# Sheet1.net
KiCad netlist of a schematic drawn in Altium Designer
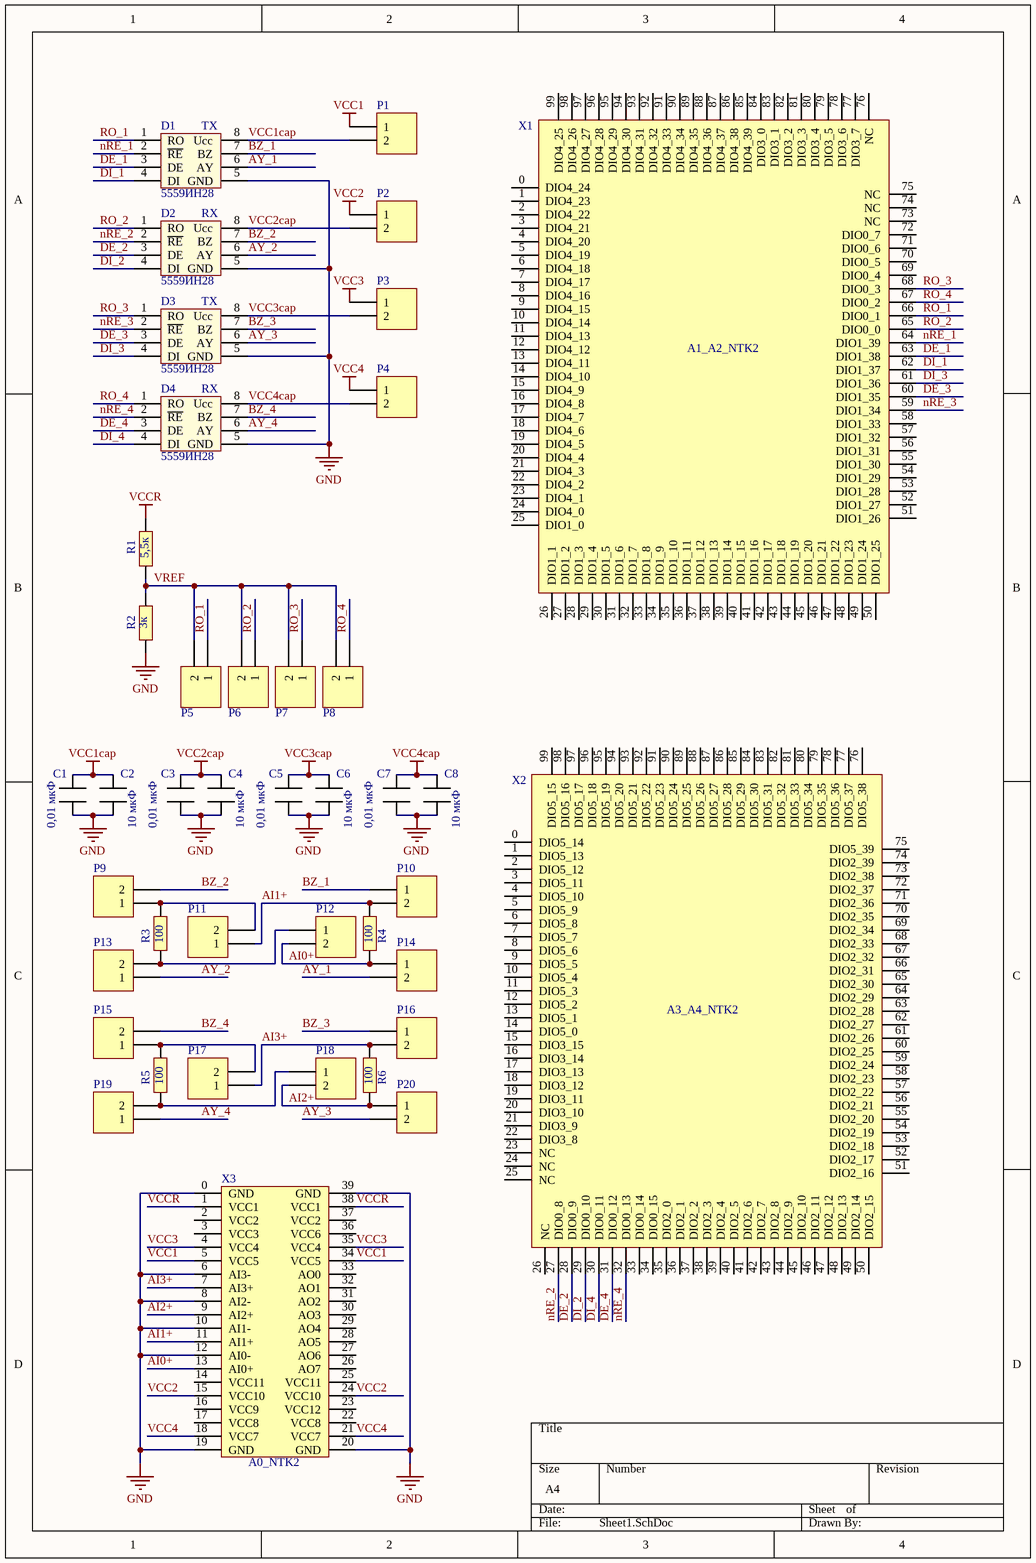
[diagram p0: Sheet1.SchDoc]

(export (version "E")
  (design (tool "Eeschema 10.0.6"))
  (components
    (comp (ref "C1") (value "0,01 мкФ") (footprint "CAP_SMALL") (libsource (lib "Schlib") (part "CAP_SMALL")))
    (comp (ref "C2") (value "10 мкФ") (footprint "Cap_BIG") (libsource (lib "Schlib") (part "CAP_BIG")))
    (comp (ref "C3") (value "0,01 мкФ") (footprint "CAP_SMALL") (libsource (lib "Schlib") (part "CAP_SMALL")))
    (comp (ref "C4") (value "10 мкФ") (footprint "Cap_BIG") (libsource (lib "Schlib") (part "CAP_BIG")))
    (comp (ref "C5") (value "0,01 мкФ") (footprint "CAP_SMALL") (libsource (lib "Schlib") (part "CAP_SMALL")))
    (comp (ref "C6") (value "10 мкФ") (footprint "Cap_BIG") (libsource (lib "Schlib") (part "CAP_BIG")))
    (comp (ref "C7") (value "0,01 мкФ") (footprint "CAP_SMALL") (libsource (lib "Schlib") (part "CAP_SMALL")))
    (comp (ref "C8") (value "10 мкФ") (footprint "Cap_BIG") (libsource (lib "Schlib") (part "CAP_BIG")))
    (comp (ref "D1") (value "5559ИН28") (footprint "5559IN28") (libsource (lib "VPL") (part "5559ИН28")))
    (comp (ref "D2") (value "5559ИН28") (footprint "5559IN28") (libsource (lib "VPL") (part "5559ИН28")))
    (comp (ref "D3") (value "5559ИН28") (footprint "5559IN28") (libsource (lib "VPL") (part "5559ИН28")))
    (comp (ref "D4") (value "5559ИН28") (footprint "5559IN28") (libsource (lib "VPL") (part "5559ИН28")))
    (comp (ref "P1")
      (value "Header 2")
      (footprint "HDR1X2")
      (description "Header, 2-Pin")
      (fields (field (name "PUBLISHER") "Altium Limited"))
      (libsource (lib "Miscellaneous Connectors") (part "Header 2"))
    )
    (comp (ref "P2")
      (value "Header 2")
      (footprint "HDR1X2")
      (description "Header, 2-Pin")
      (fields (field (name "PUBLISHER") "Altium Limited"))
      (libsource (lib "Miscellaneous Connectors") (part "Header 2"))
    )
    (comp (ref "P3")
      (value "Header 2")
      (footprint "HDR1X2")
      (description "Header, 2-Pin")
      (fields (field (name "PUBLISHER") "Altium Limited"))
      (libsource (lib "Miscellaneous Connectors") (part "Header 2"))
    )
    (comp (ref "P4")
      (value "Header 2")
      (footprint "HDR1X2")
      (description "Header, 2-Pin")
      (fields (field (name "PUBLISHER") "Altium Limited"))
      (libsource (lib "Miscellaneous Connectors") (part "Header 2"))
    )
    (comp (ref "P5")
      (value "Header 2")
      (footprint "HDR1X2")
      (description "Header, 2-Pin")
      (fields (field (name "PUBLISHER") "Altium Limited"))
      (libsource (lib "") (part "Header 2_2"))
    )
    (comp (ref "P6")
      (value "Header 2")
      (footprint "HDR1X2")
      (description "Header, 2-Pin")
      (fields (field (name "PUBLISHER") "Altium Limited"))
      (libsource (lib "") (part "Header 2_2"))
    )
    (comp (ref "P7")
      (value "Header 2")
      (footprint "HDR1X2")
      (description "Header, 2-Pin")
      (fields (field (name "PUBLISHER") "Altium Limited"))
      (libsource (lib "") (part "Header 2_2"))
    )
    (comp (ref "P8")
      (value "Header 2")
      (footprint "HDR1X2")
      (description "Header, 2-Pin")
      (fields (field (name "PUBLISHER") "Altium Limited"))
      (libsource (lib "") (part "Header 2_2"))
    )
    (comp (ref "P9")
      (value "Header 2")
      (footprint "HDR1X2")
      (description "Header, 2-Pin")
      (fields (field (name "PUBLISHER") "Altium Limited"))
      (libsource (lib "") (part "Header 2_1"))
    )
    (comp (ref "P10")
      (value "Header 2")
      (footprint "HDR1X2")
      (description "Header, 2-Pin")
      (fields (field (name "PUBLISHER") "Altium Limited"))
      (libsource (lib "Miscellaneous Connectors") (part "Header 2"))
    )
    (comp (ref "P11")
      (value "Header 2")
      (footprint "HDR1X2")
      (description "Header, 2-Pin")
      (fields (field (name "PUBLISHER") "Altium Limited"))
      (libsource (lib "") (part "Header 2_1"))
    )
    (comp (ref "P12")
      (value "Header 2")
      (footprint "HDR1X2")
      (description "Header, 2-Pin")
      (fields (field (name "PUBLISHER") "Altium Limited"))
      (libsource (lib "Miscellaneous Connectors") (part "Header 2"))
    )
    (comp (ref "P13")
      (value "Header 2")
      (footprint "HDR1X2")
      (description "Header, 2-Pin")
      (fields (field (name "PUBLISHER") "Altium Limited"))
      (libsource (lib "") (part "Header 2_1"))
    )
    (comp (ref "P14")
      (value "Header 2")
      (footprint "HDR1X2")
      (description "Header, 2-Pin")
      (fields (field (name "PUBLISHER") "Altium Limited"))
      (libsource (lib "Miscellaneous Connectors") (part "Header 2"))
    )
    (comp (ref "P15")
      (value "Header 2")
      (footprint "HDR1X2")
      (description "Header, 2-Pin")
      (fields (field (name "PUBLISHER") "Altium Limited"))
      (libsource (lib "") (part "Header 2_1"))
    )
    (comp (ref "P16")
      (value "Header 2")
      (footprint "HDR1X2")
      (description "Header, 2-Pin")
      (fields (field (name "PUBLISHER") "Altium Limited"))
      (libsource (lib "Miscellaneous Connectors") (part "Header 2"))
    )
    (comp (ref "P17")
      (value "Header 2")
      (footprint "HDR1X2")
      (description "Header, 2-Pin")
      (fields (field (name "PUBLISHER") "Altium Limited"))
      (libsource (lib "") (part "Header 2_1"))
    )
    (comp (ref "P18")
      (value "Header 2")
      (footprint "HDR1X2")
      (description "Header, 2-Pin")
      (fields (field (name "PUBLISHER") "Altium Limited"))
      (libsource (lib "Miscellaneous Connectors") (part "Header 2"))
    )
    (comp (ref "P19")
      (value "Header 2")
      (footprint "HDR1X2")
      (description "Header, 2-Pin")
      (fields (field (name "PUBLISHER") "Altium Limited"))
      (libsource (lib "") (part "Header 2_1"))
    )
    (comp (ref "P20")
      (value "Header 2")
      (footprint "HDR1X2")
      (description "Header, 2-Pin")
      (fields (field (name "PUBLISHER") "Altium Limited"))
      (libsource (lib "Miscellaneous Connectors") (part "Header 2"))
    )
    (comp (ref "R1") (value "5,5к") (footprint "RES") (libsource (lib "Schlib") (part "RES")))
    (comp (ref "R2") (value "3к") (footprint "RES") (libsource (lib "Schlib") (part "RES")))
    (comp (ref "R3") (value "100") (footprint "RES") (libsource (lib "") (part "RES_1")))
    (comp (ref "R4") (value "100") (footprint "RES") (libsource (lib "Schlib") (part "RES")))
    (comp (ref "R5") (value "100") (footprint "RES") (libsource (lib "") (part "RES_1")))
    (comp (ref "R6") (value "100") (footprint "RES") (libsource (lib "Schlib") (part "RES")))
    (comp (ref "X1")
      (value "A1_A2_NTK2")
      (footprint "A1_A2_NTK2")
      (libsource (lib "VPL") (part "A1_A2_NTK2"))
    )
    (comp (ref "X2")
      (value "A3_A4_NTK2")
      (footprint "A3_A4_NTK2")
      (libsource (lib "VPL") (part "A3_A4_NTK2"))
    )
    (comp (ref "X3") (value "A0_NTK2") (footprint "A0_NTK2") (libsource (lib "VPL") (part "A0_NTK2")))
  )
  (nets
    (net (code "1") (name "/AI0+") (class "Default")
      (node (ref "P12") (pin "2") (pinfunction "2_2") (pintype "passive"))
      (node (ref "P14") (pin "1") (pinfunction "1_1") (pintype "passive"))
      (node (ref "R4") (pin "2") (pinfunction "2_2") (pintype "passive"))
      (node (ref "X3") (pin "13") (pinfunction "AI0+_13") (pintype "power_in"))
    )
    (net (code "2") (name "/AI1+") (class "Default")
      (node (ref "P10") (pin "2") (pinfunction "2_2") (pintype "passive"))
      (node (ref "P11") (pin "1") (pinfunction "1_1") (pintype "passive"))
      (node (ref "R4") (pin "1") (pinfunction "1_1") (pintype "passive"))
      (node (ref "X3") (pin "11") (pinfunction "AI1+_11") (pintype "power_in"))
    )
    (net (code "3") (name "/AI2+") (class "Default")
      (node (ref "P18") (pin "2") (pinfunction "2_2") (pintype "passive"))
      (node (ref "P20") (pin "1") (pinfunction "1_1") (pintype "passive"))
      (node (ref "R6") (pin "2") (pinfunction "2_2") (pintype "passive"))
      (node (ref "X3") (pin "9") (pinfunction "AI2+_9") (pintype "power_in"))
    )
    (net (code "4") (name "/AI3+") (class "Default")
      (node (ref "P16") (pin "2") (pinfunction "2_2") (pintype "passive"))
      (node (ref "P17") (pin "1") (pinfunction "1_1") (pintype "passive"))
      (node (ref "R6") (pin "1") (pinfunction "1_1") (pintype "passive"))
      (node (ref "X3") (pin "7") (pinfunction "AI3+_7") (pintype "power_in"))
    )
    (net (code "5") (name "/AY_1") (class "Default")
      (node (ref "D1") (pin "6") (pinfunction "AY_6") (pintype "passive"))
      (node (ref "P14") (pin "2") (pinfunction "2_2") (pintype "passive"))
    )
    (net (code "6") (name "/AY_2") (class "Default")
      (node (ref "D2") (pin "6") (pinfunction "AY_6") (pintype "passive"))
      (node (ref "P13") (pin "1") (pinfunction "1_1") (pintype "passive"))
    )
    (net (code "7") (name "/AY_3") (class "Default")
      (node (ref "D3") (pin "6") (pinfunction "AY_6") (pintype "passive"))
      (node (ref "P20") (pin "2") (pinfunction "2_2") (pintype "passive"))
    )
    (net (code "8") (name "/AY_4") (class "Default")
      (node (ref "D4") (pin "6") (pinfunction "AY_6") (pintype "passive"))
      (node (ref "P19") (pin "1") (pinfunction "1_1") (pintype "passive"))
    )
    (net (code "9") (name "/BZ_1") (class "Default")
      (node (ref "D1") (pin "7") (pinfunction "BZ_7") (pintype "passive"))
      (node (ref "P10") (pin "1") (pinfunction "1_1") (pintype "passive"))
    )
    (net (code "10") (name "/BZ_2") (class "Default")
      (node (ref "D2") (pin "7") (pinfunction "BZ_7") (pintype "passive"))
      (node (ref "P9") (pin "2") (pinfunction "2_2") (pintype "passive"))
    )
    (net (code "11") (name "/BZ_3") (class "Default")
      (node (ref "D3") (pin "7") (pinfunction "BZ_7") (pintype "passive"))
      (node (ref "P16") (pin "1") (pinfunction "1_1") (pintype "passive"))
    )
    (net (code "12") (name "/BZ_4") (class "Default")
      (node (ref "D4") (pin "7") (pinfunction "BZ_7") (pintype "passive"))
      (node (ref "P15") (pin "2") (pinfunction "2_2") (pintype "passive"))
    )
    (net (code "13") (name "/DE_1") (class "Default")
      (node (ref "D1") (pin "3") (pinfunction "DE_3") (pintype "passive"))
      (node (ref "X1") (pin "63") (pinfunction "DIO1_38_63") (pintype "power_in"))
    )
    (net (code "14") (name "/DE_2") (class "Default")
      (node (ref "D2") (pin "3") (pinfunction "DE_3") (pintype "passive"))
      (node (ref "X2") (pin "28") (pinfunction "DIO0_9_28") (pintype "power_in"))
    )
    (net (code "15") (name "/DE_3") (class "Default")
      (node (ref "D3") (pin "3") (pinfunction "DE_3") (pintype "passive"))
      (node (ref "X1") (pin "60") (pinfunction "DIO1_35_60") (pintype "power_in"))
    )
    (net (code "16") (name "/DE_4") (class "Default")
      (node (ref "D4") (pin "3") (pinfunction "DE_3") (pintype "passive"))
      (node (ref "X2") (pin "31") (pinfunction "DIO0_12_31") (pintype "power_in"))
    )
    (net (code "17") (name "/DI_1") (class "Default")
      (node (ref "D1") (pin "4") (pinfunction "DI_4") (pintype "passive"))
      (node (ref "X1") (pin "62") (pinfunction "DIO1_37_62") (pintype "power_in"))
    )
    (net (code "18") (name "/DI_2") (class "Default")
      (node (ref "D2") (pin "4") (pinfunction "DI_4") (pintype "passive"))
      (node (ref "X2") (pin "29") (pinfunction "DIO0_10_29") (pintype "power_in"))
    )
    (net (code "19") (name "/DI_3") (class "Default")
      (node (ref "D3") (pin "4") (pinfunction "DI_4") (pintype "passive"))
      (node (ref "X1") (pin "61") (pinfunction "DIO1_36_61") (pintype "power_in"))
    )
    (net (code "20") (name "/DI_4") (class "Default")
      (node (ref "D4") (pin "4") (pinfunction "DI_4") (pintype "passive"))
      (node (ref "X2") (pin "30") (pinfunction "DIO0_11_30") (pintype "power_in"))
    )
    (net (code "21") (name "/RO_1") (class "Default")
      (node (ref "D1") (pin "1") (pinfunction "RO_1") (pintype "passive"))
      (node (ref "P5") (pin "1") (pinfunction "1_1") (pintype "passive"))
      (node (ref "X1") (pin "66") (pinfunction "DIO0_1_66") (pintype "power_in"))
    )
    (net (code "22") (name "/RO_2") (class "Default")
      (node (ref "D2") (pin "1") (pinfunction "RO_1") (pintype "passive"))
      (node (ref "P6") (pin "1") (pinfunction "1_1") (pintype "passive"))
      (node (ref "X1") (pin "65") (pinfunction "DIO0_0_65") (pintype "power_in"))
    )
    (net (code "23") (name "/RO_3") (class "Default")
      (node (ref "D3") (pin "1") (pinfunction "RO_1") (pintype "passive"))
      (node (ref "P7") (pin "1") (pinfunction "1_1") (pintype "passive"))
      (node (ref "X1") (pin "68") (pinfunction "DIO0_3_68") (pintype "power_in"))
    )
    (net (code "24") (name "/RO_4") (class "Default")
      (node (ref "D4") (pin "1") (pinfunction "RO_1") (pintype "passive"))
      (node (ref "P8") (pin "1") (pinfunction "1_1") (pintype "passive"))
      (node (ref "X1") (pin "67") (pinfunction "DIO0_2_67") (pintype "power_in"))
    )
    (net (code "25") (name "/VREF") (class "Default")
      (node (ref "P5") (pin "2") (pinfunction "2_2") (pintype "passive"))
      (node (ref "P6") (pin "2") (pinfunction "2_2") (pintype "passive"))
      (node (ref "P7") (pin "2") (pinfunction "2_2") (pintype "passive"))
      (node (ref "P8") (pin "2") (pinfunction "2_2") (pintype "passive"))
      (node (ref "R1") (pin "2") (pinfunction "2_2") (pintype "passive"))
      (node (ref "R2") (pin "1") (pinfunction "1_1") (pintype "passive"))
    )
    (net (code "26") (name "/nRE_1") (class "Default")
      (node (ref "D1") (pin "2") (pinfunction "~{RE}_2") (pintype "passive"))
      (node (ref "X1") (pin "64") (pinfunction "DIO1_39_64") (pintype "power_in"))
    )
    (net (code "27") (name "/nRE_2") (class "Default")
      (node (ref "D2") (pin "2") (pinfunction "~{RE}_2") (pintype "passive"))
      (node (ref "X2") (pin "27") (pinfunction "DIO0_8_27") (pintype "power_in"))
    )
    (net (code "28") (name "/nRE_3") (class "Default")
      (node (ref "D3") (pin "2") (pinfunction "~{RE}_2") (pintype "passive"))
      (node (ref "X1") (pin "59") (pinfunction "DIO1_34_59") (pintype "power_in"))
    )
    (net (code "29") (name "/nRE_4") (class "Default")
      (node (ref "D4") (pin "2") (pinfunction "~{RE}_2") (pintype "passive"))
      (node (ref "X2") (pin "32") (pinfunction "DIO0_13_32") (pintype "power_in"))
    )
    (net (code "30") (name "GND") (class "Default")
      (node (ref "C1") (pin "1") (pinfunction "1_1") (pintype "passive"))
      (node (ref "C2") (pin "1") (pinfunction "1_1") (pintype "passive"))
      (node (ref "C3") (pin "1") (pinfunction "1_1") (pintype "passive"))
      (node (ref "C4") (pin "1") (pinfunction "1_1") (pintype "passive"))
      (node (ref "C5") (pin "1") (pinfunction "1_1") (pintype "passive"))
      (node (ref "C6") (pin "1") (pinfunction "1_1") (pintype "passive"))
      (node (ref "C7") (pin "1") (pinfunction "1_1") (pintype "passive"))
      (node (ref "C8") (pin "1") (pinfunction "1_1") (pintype "passive"))
      (node (ref "D1") (pin "5") (pinfunction "GND_5") (pintype "passive"))
      (node (ref "D2") (pin "5") (pinfunction "GND_5") (pintype "passive"))
      (node (ref "D3") (pin "5") (pinfunction "GND_5") (pintype "passive"))
      (node (ref "D4") (pin "5") (pinfunction "GND_5") (pintype "passive"))
      (node (ref "R2") (pin "2") (pinfunction "2_2") (pintype "passive"))
      (node (ref "X3") (pin "0") (pinfunction "GND_0") (pintype "power_in"))
      (node (ref "X3") (pin "10") (pinfunction "AI1-_10") (pintype "power_in"))
      (node (ref "X3") (pin "12") (pinfunction "AI0-_12") (pintype "power_in"))
      (node (ref "X3") (pin "19") (pinfunction "GND_19") (pintype "power_in"))
      (node (ref "X3") (pin "20") (pinfunction "GND_20") (pintype "power_in"))
      (node (ref "X3") (pin "39") (pinfunction "GND_39") (pintype "power_in"))
      (node (ref "X3") (pin "6") (pinfunction "AI3-_6") (pintype "power_in"))
      (node (ref "X3") (pin "8") (pinfunction "AI2-_8") (pintype "power_in"))
    )
    (net (code "31") (name "Net-(P11-Pad2)") (class "Default")
      (node (ref "P11") (pin "2") (pinfunction "2_2") (pintype "passive"))
      (node (ref "P9") (pin "1") (pinfunction "1_1") (pintype "passive"))
      (node (ref "R3") (pin "2") (pinfunction "2_2") (pintype "passive"))
    )
    (net (code "32") (name "Net-(P12-Pad1)") (class "Default")
      (node (ref "P12") (pin "1") (pinfunction "1_1") (pintype "passive"))
      (node (ref "P13") (pin "2") (pinfunction "2_2") (pintype "passive"))
      (node (ref "R3") (pin "1") (pinfunction "1_1") (pintype "passive"))
    )
    (net (code "33") (name "Net-(P15-Pad1)") (class "Default")
      (node (ref "P15") (pin "1") (pinfunction "1_1") (pintype "passive"))
      (node (ref "P17") (pin "2") (pinfunction "2_2") (pintype "passive"))
      (node (ref "R5") (pin "2") (pinfunction "2_2") (pintype "passive"))
    )
    (net (code "34") (name "Net-(P18-Pad1)") (class "Default")
      (node (ref "P18") (pin "1") (pinfunction "1_1") (pintype "passive"))
      (node (ref "P19") (pin "2") (pinfunction "2_2") (pintype "passive"))
      (node (ref "R5") (pin "1") (pinfunction "1_1") (pintype "passive"))
    )
    (net (code "35") (name "VCC1") (class "Default")
      (node (ref "P1") (pin "1") (pinfunction "1_1") (pintype "passive"))
      (node (ref "X3") (pin "34") (pinfunction "VCC5_34") (pintype "power_in"))
      (node (ref "X3") (pin "5") (pinfunction "VCC5_5") (pintype "power_in"))
    )
    (net (code "36") (name "VCC1cap") (class "Default")
      (node (ref "C1") (pin "2") (pinfunction "2_2") (pintype "passive"))
      (node (ref "C2") (pin "2") (pinfunction "2_2") (pintype "passive"))
      (node (ref "D1") (pin "8") (pinfunction "Ucc_8") (pintype "passive"))
      (node (ref "P1") (pin "2") (pinfunction "2_2") (pintype "passive"))
    )
    (net (code "37") (name "VCC2") (class "Default")
      (node (ref "P2") (pin "1") (pinfunction "1_1") (pintype "passive"))
      (node (ref "X3") (pin "15") (pinfunction "VCC10_15") (pintype "power_in"))
      (node (ref "X3") (pin "24") (pinfunction "VCC10_24") (pintype "power_in"))
    )
    (net (code "38") (name "VCC2cap") (class "Default")
      (node (ref "C3") (pin "2") (pinfunction "2_2") (pintype "passive"))
      (node (ref "C4") (pin "2") (pinfunction "2_2") (pintype "passive"))
      (node (ref "D2") (pin "8") (pinfunction "Ucc_8") (pintype "passive"))
      (node (ref "P2") (pin "2") (pinfunction "2_2") (pintype "passive"))
    )
    (net (code "39") (name "VCC3") (class "Default")
      (node (ref "P3") (pin "1") (pinfunction "1_1") (pintype "passive"))
      (node (ref "X3") (pin "35") (pinfunction "VCC4_35") (pintype "power_in"))
      (node (ref "X3") (pin "4") (pinfunction "VCC4_4") (pintype "power_in"))
    )
    (net (code "40") (name "VCC3cap") (class "Default")
      (node (ref "C5") (pin "2") (pinfunction "2_2") (pintype "passive"))
      (node (ref "C6") (pin "2") (pinfunction "2_2") (pintype "passive"))
      (node (ref "D3") (pin "8") (pinfunction "Ucc_8") (pintype "passive"))
      (node (ref "P3") (pin "2") (pinfunction "2_2") (pintype "passive"))
    )
    (net (code "41") (name "VCC4") (class "Default")
      (node (ref "P4") (pin "1") (pinfunction "1_1") (pintype "passive"))
      (node (ref "X3") (pin "18") (pinfunction "VCC7_18") (pintype "power_in"))
      (node (ref "X3") (pin "21") (pinfunction "VCC7_21") (pintype "power_in"))
    )
    (net (code "42") (name "VCC4cap") (class "Default")
      (node (ref "C7") (pin "2") (pinfunction "2_2") (pintype "passive"))
      (node (ref "C8") (pin "2") (pinfunction "2_2") (pintype "passive"))
      (node (ref "D4") (pin "8") (pinfunction "Ucc_8") (pintype "passive"))
      (node (ref "P4") (pin "2") (pinfunction "2_2") (pintype "passive"))
    )
    (net (code "43") (name "VCCR") (class "Default")
      (node (ref "R1") (pin "1") (pinfunction "1_1") (pintype "passive"))
      (node (ref "X3") (pin "1") (pinfunction "VCC1_1") (pintype "power_in"))
      (node (ref "X3") (pin "38") (pinfunction "VCC1_38") (pintype "power_in"))
    )
    (net (code "44") (name "unconnected-(X1-DIO0_4-Pad69)") (class "Default")
      (node (ref "X1") (pin "69") (pinfunction "DIO0_4_69") (pintype "power_in"))
    )
    (net (code "45") (name "unconnected-(X1-DIO0_5-Pad70)") (class "Default")
      (node (ref "X1") (pin "70") (pinfunction "DIO0_5_70") (pintype "power_in"))
    )
    (net (code "46") (name "unconnected-(X1-DIO0_6-Pad71)") (class "Default")
      (node (ref "X1") (pin "71") (pinfunction "DIO0_6_71") (pintype "power_in"))
    )
    (net (code "47") (name "unconnected-(X1-DIO0_7-Pad72)") (class "Default")
      (node (ref "X1") (pin "72") (pinfunction "DIO0_7_72") (pintype "power_in"))
    )
    (net (code "48") (name "unconnected-(X1-DIO1_0-Pad25)") (class "Default")
      (node (ref "X1") (pin "25") (pinfunction "DIO1_0_25") (pintype "power_in"))
    )
    (net (code "49") (name "unconnected-(X1-DIO1_1-Pad26)") (class "Default")
      (node (ref "X1") (pin "26") (pinfunction "DIO1_1_26") (pintype "power_in"))
    )
    (net (code "50") (name "unconnected-(X1-DIO1_2-Pad27)") (class "Default")
      (node (ref "X1") (pin "27") (pinfunction "DIO1_2_27") (pintype "power_in"))
    )
    (net (code "51") (name "unconnected-(X1-DIO1_3-Pad28)") (class "Default")
      (node (ref "X1") (pin "28") (pinfunction "DIO1_3_28") (pintype "power_in"))
    )
    (net (code "52") (name "unconnected-(X1-DIO1_4-Pad29)") (class "Default")
      (node (ref "X1") (pin "29") (pinfunction "DIO1_4_29") (pintype "power_in"))
    )
    (net (code "53") (name "unconnected-(X1-DIO1_5-Pad30)") (class "Default")
      (node (ref "X1") (pin "30") (pinfunction "DIO1_5_30") (pintype "power_in"))
    )
    (net (code "54") (name "unconnected-(X1-DIO1_6-Pad31)") (class "Default")
      (node (ref "X1") (pin "31") (pinfunction "DIO1_6_31") (pintype "power_in"))
    )
    (net (code "55") (name "unconnected-(X1-DIO1_7-Pad32)") (class "Default")
      (node (ref "X1") (pin "32") (pinfunction "DIO1_7_32") (pintype "power_in"))
    )
    (net (code "56") (name "unconnected-(X1-DIO1_8-Pad33)") (class "Default")
      (node (ref "X1") (pin "33") (pinfunction "DIO1_8_33") (pintype "power_in"))
    )
    (net (code "57") (name "unconnected-(X1-DIO1_9-Pad34)") (class "Default")
      (node (ref "X1") (pin "34") (pinfunction "DIO1_9_34") (pintype "power_in"))
    )
    (net (code "58") (name "unconnected-(X1-DIO1_10-Pad35)") (class "Default")
      (node (ref "X1") (pin "35") (pinfunction "DIO1_10_35") (pintype "power_in"))
    )
    (net (code "59") (name "unconnected-(X1-DIO1_11-Pad36)") (class "Default")
      (node (ref "X1") (pin "36") (pinfunction "DIO1_11_36") (pintype "power_in"))
    )
    (net (code "60") (name "unconnected-(X1-DIO1_12-Pad37)") (class "Default")
      (node (ref "X1") (pin "37") (pinfunction "DIO1_12_37") (pintype "power_in"))
    )
    (net (code "61") (name "unconnected-(X1-DIO1_13-Pad38)") (class "Default")
      (node (ref "X1") (pin "38") (pinfunction "DIO1_13_38") (pintype "power_in"))
    )
    (net (code "62") (name "unconnected-(X1-DIO1_14-Pad39)") (class "Default")
      (node (ref "X1") (pin "39") (pinfunction "DIO1_14_39") (pintype "power_in"))
    )
    (net (code "63") (name "unconnected-(X1-DIO1_15-Pad40)") (class "Default")
      (node (ref "X1") (pin "40") (pinfunction "DIO1_15_40") (pintype "power_in"))
    )
    (net (code "64") (name "unconnected-(X1-DIO1_16-Pad41)") (class "Default")
      (node (ref "X1") (pin "41") (pinfunction "DIO1_16_41") (pintype "power_in"))
    )
    (net (code "65") (name "unconnected-(X1-DIO1_17-Pad42)") (class "Default")
      (node (ref "X1") (pin "42") (pinfunction "DIO1_17_42") (pintype "power_in"))
    )
    (net (code "66") (name "unconnected-(X1-DIO1_18-Pad43)") (class "Default")
      (node (ref "X1") (pin "43") (pinfunction "DIO1_18_43") (pintype "power_in"))
    )
    (net (code "67") (name "unconnected-(X1-DIO1_19-Pad44)") (class "Default")
      (node (ref "X1") (pin "44") (pinfunction "DIO1_19_44") (pintype "power_in"))
    )
    (net (code "68") (name "unconnected-(X1-DIO1_20-Pad45)") (class "Default")
      (node (ref "X1") (pin "45") (pinfunction "DIO1_20_45") (pintype "power_in"))
    )
    (net (code "69") (name "unconnected-(X1-DIO1_21-Pad46)") (class "Default")
      (node (ref "X1") (pin "46") (pinfunction "DIO1_21_46") (pintype "power_in"))
    )
    (net (code "70") (name "unconnected-(X1-DIO1_22-Pad47)") (class "Default")
      (node (ref "X1") (pin "47") (pinfunction "DIO1_22_47") (pintype "power_in"))
    )
    (net (code "71") (name "unconnected-(X1-DIO1_23-Pad48)") (class "Default")
      (node (ref "X1") (pin "48") (pinfunction "DIO1_23_48") (pintype "power_in"))
    )
    (net (code "72") (name "unconnected-(X1-DIO1_24-Pad49)") (class "Default")
      (node (ref "X1") (pin "49") (pinfunction "DIO1_24_49") (pintype "power_in"))
    )
    (net (code "73") (name "unconnected-(X1-DIO1_25-Pad50)") (class "Default")
      (node (ref "X1") (pin "50") (pinfunction "DIO1_25_50") (pintype "power_in"))
    )
    (net (code "74") (name "unconnected-(X1-DIO1_26-Pad51)") (class "Default")
      (node (ref "X1") (pin "51") (pinfunction "DIO1_26_51") (pintype "power_in"))
    )
    (net (code "75") (name "unconnected-(X1-DIO1_27-Pad52)") (class "Default")
      (node (ref "X1") (pin "52") (pinfunction "DIO1_27_52") (pintype "power_in"))
    )
    (net (code "76") (name "unconnected-(X1-DIO1_28-Pad53)") (class "Default")
      (node (ref "X1") (pin "53") (pinfunction "DIO1_28_53") (pintype "power_in"))
    )
    (net (code "77") (name "unconnected-(X1-DIO1_29-Pad54)") (class "Default")
      (node (ref "X1") (pin "54") (pinfunction "DIO1_29_54") (pintype "power_in"))
    )
    (net (code "78") (name "unconnected-(X1-DIO1_30-Pad55)") (class "Default")
      (node (ref "X1") (pin "55") (pinfunction "DIO1_30_55") (pintype "power_in"))
    )
    (net (code "79") (name "unconnected-(X1-DIO1_31-Pad56)") (class "Default")
      (node (ref "X1") (pin "56") (pinfunction "DIO1_31_56") (pintype "power_in"))
    )
    (net (code "80") (name "unconnected-(X1-DIO1_32-Pad57)") (class "Default")
      (node (ref "X1") (pin "57") (pinfunction "DIO1_32_57") (pintype "power_in"))
    )
    (net (code "81") (name "unconnected-(X1-DIO1_33-Pad58)") (class "Default")
      (node (ref "X1") (pin "58") (pinfunction "DIO1_33_58") (pintype "power_in"))
    )
    (net (code "82") (name "unconnected-(X1-DIO3_0-Pad84)") (class "Default")
      (node (ref "X1") (pin "84") (pinfunction "DIO3_0_84") (pintype "power_in"))
    )
    (net (code "83") (name "unconnected-(X1-DIO3_1-Pad83)") (class "Default")
      (node (ref "X1") (pin "83") (pinfunction "DIO3_1_83") (pintype "power_in"))
    )
    (net (code "84") (name "unconnected-(X1-DIO3_2-Pad82)") (class "Default")
      (node (ref "X1") (pin "82") (pinfunction "DIO3_2_82") (pintype "power_in"))
    )
    (net (code "85") (name "unconnected-(X1-DIO3_3-Pad81)") (class "Default")
      (node (ref "X1") (pin "81") (pinfunction "DIO3_3_81") (pintype "power_in"))
    )
    (net (code "86") (name "unconnected-(X1-DIO3_4-Pad80)") (class "Default")
      (node (ref "X1") (pin "80") (pinfunction "DIO3_4_80") (pintype "power_in"))
    )
    (net (code "87") (name "unconnected-(X1-DIO3_5-Pad79)") (class "Default")
      (node (ref "X1") (pin "79") (pinfunction "DIO3_5_79") (pintype "power_in"))
    )
    (net (code "88") (name "unconnected-(X1-DIO3_6-Pad78)") (class "Default")
      (node (ref "X1") (pin "78") (pinfunction "DIO3_6_78") (pintype "power_in"))
    )
    (net (code "89") (name "unconnected-(X1-DIO3_7-Pad77)") (class "Default")
      (node (ref "X1") (pin "77") (pinfunction "DIO3_7_77") (pintype "power_in"))
    )
    (net (code "90") (name "unconnected-(X1-DIO4_0-Pad24)") (class "Default")
      (node (ref "X1") (pin "24") (pinfunction "DIO4_0_24") (pintype "power_in"))
    )
    (net (code "91") (name "unconnected-(X1-DIO4_1-Pad23)") (class "Default")
      (node (ref "X1") (pin "23") (pinfunction "DIO4_1_23") (pintype "power_in"))
    )
    (net (code "92") (name "unconnected-(X1-DIO4_2-Pad22)") (class "Default")
      (node (ref "X1") (pin "22") (pinfunction "DIO4_2_22") (pintype "power_in"))
    )
    (net (code "93") (name "unconnected-(X1-DIO4_3-Pad21)") (class "Default")
      (node (ref "X1") (pin "21") (pinfunction "DIO4_3_21") (pintype "power_in"))
    )
    (net (code "94") (name "unconnected-(X1-DIO4_4-Pad20)") (class "Default")
      (node (ref "X1") (pin "20") (pinfunction "DIO4_4_20") (pintype "power_in"))
    )
    (net (code "95") (name "unconnected-(X1-DIO4_5-Pad19)") (class "Default")
      (node (ref "X1") (pin "19") (pinfunction "DIO4_5_19") (pintype "power_in"))
    )
    (net (code "96") (name "unconnected-(X1-DIO4_6-Pad18)") (class "Default")
      (node (ref "X1") (pin "18") (pinfunction "DIO4_6_18") (pintype "power_in"))
    )
    (net (code "97") (name "unconnected-(X1-DIO4_7-Pad17)") (class "Default")
      (node (ref "X1") (pin "17") (pinfunction "DIO4_7_17") (pintype "power_in"))
    )
    (net (code "98") (name "unconnected-(X1-DIO4_8-Pad16)") (class "Default")
      (node (ref "X1") (pin "16") (pinfunction "DIO4_8_16") (pintype "power_in"))
    )
    (net (code "99") (name "unconnected-(X1-DIO4_9-Pad15)") (class "Default")
      (node (ref "X1") (pin "15") (pinfunction "DIO4_9_15") (pintype "power_in"))
    )
    (net (code "100") (name "unconnected-(X1-DIO4_10-Pad14)") (class "Default")
      (node (ref "X1") (pin "14") (pinfunction "DIO4_10_14") (pintype "power_in"))
    )
    (net (code "101") (name "unconnected-(X1-DIO4_11-Pad13)") (class "Default")
      (node (ref "X1") (pin "13") (pinfunction "DIO4_11_13") (pintype "power_in"))
    )
    (net (code "102") (name "unconnected-(X1-DIO4_12-Pad12)") (class "Default")
      (node (ref "X1") (pin "12") (pinfunction "DIO4_12_12") (pintype "power_in"))
    )
    (net (code "103") (name "unconnected-(X1-DIO4_13-Pad11)") (class "Default")
      (node (ref "X1") (pin "11") (pinfunction "DIO4_13_11") (pintype "power_in"))
    )
    (net (code "104") (name "unconnected-(X1-DIO4_14-Pad10)") (class "Default")
      (node (ref "X1") (pin "10") (pinfunction "DIO4_14_10") (pintype "power_in"))
    )
    (net (code "105") (name "unconnected-(X1-DIO4_15-Pad9)") (class "Default")
      (node (ref "X1") (pin "9") (pinfunction "DIO4_15_9") (pintype "power_in"))
    )
    (net (code "106") (name "unconnected-(X1-DIO4_16-Pad8)") (class "Default")
      (node (ref "X1") (pin "8") (pinfunction "DIO4_16_8") (pintype "power_in"))
    )
    (net (code "107") (name "unconnected-(X1-DIO4_17-Pad7)") (class "Default")
      (node (ref "X1") (pin "7") (pinfunction "DIO4_17_7") (pintype "power_in"))
    )
    (net (code "108") (name "unconnected-(X1-DIO4_18-Pad6)") (class "Default")
      (node (ref "X1") (pin "6") (pinfunction "DIO4_18_6") (pintype "power_in"))
    )
    (net (code "109") (name "unconnected-(X1-DIO4_19-Pad5)") (class "Default")
      (node (ref "X1") (pin "5") (pinfunction "DIO4_19_5") (pintype "power_in"))
    )
    (net (code "110") (name "unconnected-(X1-DIO4_20-Pad4)") (class "Default")
      (node (ref "X1") (pin "4") (pinfunction "DIO4_20_4") (pintype "power_in"))
    )
    (net (code "111") (name "unconnected-(X1-DIO4_21-Pad3)") (class "Default")
      (node (ref "X1") (pin "3") (pinfunction "DIO4_21_3") (pintype "power_in"))
    )
    (net (code "112") (name "unconnected-(X1-DIO4_22-Pad2)") (class "Default")
      (node (ref "X1") (pin "2") (pinfunction "DIO4_22_2") (pintype "power_in"))
    )
    (net (code "113") (name "unconnected-(X1-DIO4_23-Pad1)") (class "Default")
      (node (ref "X1") (pin "1") (pinfunction "DIO4_23_1") (pintype "power_in"))
    )
    (net (code "114") (name "unconnected-(X1-DIO4_24-Pad0)") (class "Default")
      (node (ref "X1") (pin "0") (pinfunction "DIO4_24_0") (pintype "power_in"))
    )
    (net (code "115") (name "unconnected-(X1-DIO4_25-Pad99)") (class "Default")
      (node (ref "X1") (pin "99") (pinfunction "DIO4_25_99") (pintype "power_in"))
    )
    (net (code "116") (name "unconnected-(X1-DIO4_26-Pad98)") (class "Default")
      (node (ref "X1") (pin "98") (pinfunction "DIO4_26_98") (pintype "power_in"))
    )
    (net (code "117") (name "unconnected-(X1-DIO4_27-Pad97)") (class "Default")
      (node (ref "X1") (pin "97") (pinfunction "DIO4_27_97") (pintype "power_in"))
    )
    (net (code "118") (name "unconnected-(X1-DIO4_28-Pad96)") (class "Default")
      (node (ref "X1") (pin "96") (pinfunction "DIO4_28_96") (pintype "power_in"))
    )
    (net (code "119") (name "unconnected-(X1-DIO4_29-Pad95)") (class "Default")
      (node (ref "X1") (pin "95") (pinfunction "DIO4_29_95") (pintype "power_in"))
    )
    (net (code "120") (name "unconnected-(X1-DIO4_30-Pad94)") (class "Default")
      (node (ref "X1") (pin "94") (pinfunction "DIO4_30_94") (pintype "power_in"))
    )
    (net (code "121") (name "unconnected-(X1-DIO4_31-Pad93)") (class "Default")
      (node (ref "X1") (pin "93") (pinfunction "DIO4_31_93") (pintype "power_in"))
    )
    (net (code "122") (name "unconnected-(X1-DIO4_32-Pad92)") (class "Default")
      (node (ref "X1") (pin "92") (pinfunction "DIO4_32_92") (pintype "power_in"))
    )
    (net (code "123") (name "unconnected-(X1-DIO4_33-Pad91)") (class "Default")
      (node (ref "X1") (pin "91") (pinfunction "DIO4_33_91") (pintype "power_in"))
    )
    (net (code "124") (name "unconnected-(X1-DIO4_34-Pad90)") (class "Default")
      (node (ref "X1") (pin "90") (pinfunction "DIO4_34_90") (pintype "power_in"))
    )
    (net (code "125") (name "unconnected-(X1-DIO4_35-Pad89)") (class "Default")
      (node (ref "X1") (pin "89") (pinfunction "DIO4_35_89") (pintype "power_in"))
    )
    (net (code "126") (name "unconnected-(X1-DIO4_36-Pad88)") (class "Default")
      (node (ref "X1") (pin "88") (pinfunction "DIO4_36_88") (pintype "power_in"))
    )
    (net (code "127") (name "unconnected-(X1-DIO4_37-Pad87)") (class "Default")
      (node (ref "X1") (pin "87") (pinfunction "DIO4_37_87") (pintype "power_in"))
    )
    (net (code "128") (name "unconnected-(X1-DIO4_38-Pad86)") (class "Default")
      (node (ref "X1") (pin "86") (pinfunction "DIO4_38_86") (pintype "power_in"))
    )
    (net (code "129") (name "unconnected-(X1-DIO4_39-Pad85)") (class "Default")
      (node (ref "X1") (pin "85") (pinfunction "DIO4_39_85") (pintype "power_in"))
    )
    (net (code "130") (name "unconnected-(X1-NC-Pad73)") (class "Default")
      (node (ref "X1") (pin "73") (pinfunction "NC_73") (pintype "power_in"))
    )
    (net (code "131") (name "unconnected-(X1-NC-Pad74)") (class "Default")
      (node (ref "X1") (pin "74") (pinfunction "NC_74") (pintype "power_in"))
    )
    (net (code "132") (name "unconnected-(X1-NC-Pad75)") (class "Default")
      (node (ref "X1") (pin "75") (pinfunction "NC_75") (pintype "power_in"))
    )
    (net (code "133") (name "unconnected-(X1-NC-Pad76)") (class "Default")
      (node (ref "X1") (pin "76") (pinfunction "NC_76") (pintype "power_in"))
    )
    (net (code "134") (name "unconnected-(X2-DIO0_14-Pad33)") (class "Default")
      (node (ref "X2") (pin "33") (pinfunction "DIO0_14_33") (pintype "power_in"))
    )
    (net (code "135") (name "unconnected-(X2-DIO0_15-Pad34)") (class "Default")
      (node (ref "X2") (pin "34") (pinfunction "DIO0_15_34") (pintype "power_in"))
    )
    (net (code "136") (name "unconnected-(X2-DIO2_0-Pad35)") (class "Default")
      (node (ref "X2") (pin "35") (pinfunction "DIO2_0_35") (pintype "power_in"))
    )
    (net (code "137") (name "unconnected-(X2-DIO2_1-Pad36)") (class "Default")
      (node (ref "X2") (pin "36") (pinfunction "DIO2_1_36") (pintype "power_in"))
    )
    (net (code "138") (name "unconnected-(X2-DIO2_2-Pad37)") (class "Default")
      (node (ref "X2") (pin "37") (pinfunction "DIO2_2_37") (pintype "power_in"))
    )
    (net (code "139") (name "unconnected-(X2-DIO2_3-Pad38)") (class "Default")
      (node (ref "X2") (pin "38") (pinfunction "DIO2_3_38") (pintype "power_in"))
    )
    (net (code "140") (name "unconnected-(X2-DIO2_4-Pad39)") (class "Default")
      (node (ref "X2") (pin "39") (pinfunction "DIO2_4_39") (pintype "power_in"))
    )
    (net (code "141") (name "unconnected-(X2-DIO2_5-Pad40)") (class "Default")
      (node (ref "X2") (pin "40") (pinfunction "DIO2_5_40") (pintype "power_in"))
    )
    (net (code "142") (name "unconnected-(X2-DIO2_6-Pad41)") (class "Default")
      (node (ref "X2") (pin "41") (pinfunction "DIO2_6_41") (pintype "power_in"))
    )
    (net (code "143") (name "unconnected-(X2-DIO2_7-Pad42)") (class "Default")
      (node (ref "X2") (pin "42") (pinfunction "DIO2_7_42") (pintype "power_in"))
    )
    (net (code "144") (name "unconnected-(X2-DIO2_8-Pad43)") (class "Default")
      (node (ref "X2") (pin "43") (pinfunction "DIO2_8_43") (pintype "power_in"))
    )
    (net (code "145") (name "unconnected-(X2-DIO2_9-Pad44)") (class "Default")
      (node (ref "X2") (pin "44") (pinfunction "DIO2_9_44") (pintype "power_in"))
    )
    (net (code "146") (name "unconnected-(X2-DIO2_10-Pad45)") (class "Default")
      (node (ref "X2") (pin "45") (pinfunction "DIO2_10_45") (pintype "power_in"))
    )
    (net (code "147") (name "unconnected-(X2-DIO2_11-Pad46)") (class "Default")
      (node (ref "X2") (pin "46") (pinfunction "DIO2_11_46") (pintype "power_in"))
    )
    (net (code "148") (name "unconnected-(X2-DIO2_12-Pad47)") (class "Default")
      (node (ref "X2") (pin "47") (pinfunction "DIO2_12_47") (pintype "power_in"))
    )
    (net (code "149") (name "unconnected-(X2-DIO2_13-Pad48)") (class "Default")
      (node (ref "X2") (pin "48") (pinfunction "DIO2_13_48") (pintype "power_in"))
    )
    (net (code "150") (name "unconnected-(X2-DIO2_14-Pad49)") (class "Default")
      (node (ref "X2") (pin "49") (pinfunction "DIO2_14_49") (pintype "power_in"))
    )
    (net (code "151") (name "unconnected-(X2-DIO2_15-Pad50)") (class "Default")
      (node (ref "X2") (pin "50") (pinfunction "DIO2_15_50") (pintype "power_in"))
    )
    (net (code "152") (name "unconnected-(X2-DIO2_16-Pad51)") (class "Default")
      (node (ref "X2") (pin "51") (pinfunction "DIO2_16_51") (pintype "power_in"))
    )
    (net (code "153") (name "unconnected-(X2-DIO2_17-Pad52)") (class "Default")
      (node (ref "X2") (pin "52") (pinfunction "DIO2_17_52") (pintype "power_in"))
    )
    (net (code "154") (name "unconnected-(X2-DIO2_18-Pad53)") (class "Default")
      (node (ref "X2") (pin "53") (pinfunction "DIO2_18_53") (pintype "power_in"))
    )
    (net (code "155") (name "unconnected-(X2-DIO2_19-Pad54)") (class "Default")
      (node (ref "X2") (pin "54") (pinfunction "DIO2_19_54") (pintype "power_in"))
    )
    (net (code "156") (name "unconnected-(X2-DIO2_20-Pad55)") (class "Default")
      (node (ref "X2") (pin "55") (pinfunction "DIO2_20_55") (pintype "power_in"))
    )
    (net (code "157") (name "unconnected-(X2-DIO2_21-Pad56)") (class "Default")
      (node (ref "X2") (pin "56") (pinfunction "DIO2_21_56") (pintype "power_in"))
    )
    (net (code "158") (name "unconnected-(X2-DIO2_22-Pad57)") (class "Default")
      (node (ref "X2") (pin "57") (pinfunction "DIO2_22_57") (pintype "power_in"))
    )
    (net (code "159") (name "unconnected-(X2-DIO2_23-Pad58)") (class "Default")
      (node (ref "X2") (pin "58") (pinfunction "DIO2_23_58") (pintype "power_in"))
    )
    (net (code "160") (name "unconnected-(X2-DIO2_24-Pad59)") (class "Default")
      (node (ref "X2") (pin "59") (pinfunction "DIO2_24_59") (pintype "power_in"))
    )
    (net (code "161") (name "unconnected-(X2-DIO2_25-Pad60)") (class "Default")
      (node (ref "X2") (pin "60") (pinfunction "DIO2_25_60") (pintype "power_in"))
    )
    (net (code "162") (name "unconnected-(X2-DIO2_26-Pad61)") (class "Default")
      (node (ref "X2") (pin "61") (pinfunction "DIO2_26_61") (pintype "power_in"))
    )
    (net (code "163") (name "unconnected-(X2-DIO2_27-Pad62)") (class "Default")
      (node (ref "X2") (pin "62") (pinfunction "DIO2_27_62") (pintype "power_in"))
    )
    (net (code "164") (name "unconnected-(X2-DIO2_28-Pad63)") (class "Default")
      (node (ref "X2") (pin "63") (pinfunction "DIO2_28_63") (pintype "power_in"))
    )
    (net (code "165") (name "unconnected-(X2-DIO2_29-Pad64)") (class "Default")
      (node (ref "X2") (pin "64") (pinfunction "DIO2_29_64") (pintype "power_in"))
    )
    (net (code "166") (name "unconnected-(X2-DIO2_30-Pad65)") (class "Default")
      (node (ref "X2") (pin "65") (pinfunction "DIO2_30_65") (pintype "power_in"))
    )
    (net (code "167") (name "unconnected-(X2-DIO2_31-Pad66)") (class "Default")
      (node (ref "X2") (pin "66") (pinfunction "DIO2_31_66") (pintype "power_in"))
    )
    (net (code "168") (name "unconnected-(X2-DIO2_32-Pad67)") (class "Default")
      (node (ref "X2") (pin "67") (pinfunction "DIO2_32_67") (pintype "power_in"))
    )
    (net (code "169") (name "unconnected-(X2-DIO2_33-Pad68)") (class "Default")
      (node (ref "X2") (pin "68") (pinfunction "DIO2_33_68") (pintype "power_in"))
    )
    (net (code "170") (name "unconnected-(X2-DIO2_34-Pad69)") (class "Default")
      (node (ref "X2") (pin "69") (pinfunction "DIO2_34_69") (pintype "power_in"))
    )
    (net (code "171") (name "unconnected-(X2-DIO2_35-Pad70)") (class "Default")
      (node (ref "X2") (pin "70") (pinfunction "DIO2_35_70") (pintype "power_in"))
    )
    (net (code "172") (name "unconnected-(X2-DIO2_36-Pad71)") (class "Default")
      (node (ref "X2") (pin "71") (pinfunction "DIO2_36_71") (pintype "power_in"))
    )
    (net (code "173") (name "unconnected-(X2-DIO2_37-Pad72)") (class "Default")
      (node (ref "X2") (pin "72") (pinfunction "DIO2_37_72") (pintype "power_in"))
    )
    (net (code "174") (name "unconnected-(X2-DIO2_38-Pad73)") (class "Default")
      (node (ref "X2") (pin "73") (pinfunction "DIO2_38_73") (pintype "power_in"))
    )
    (net (code "175") (name "unconnected-(X2-DIO2_39-Pad74)") (class "Default")
      (node (ref "X2") (pin "74") (pinfunction "DIO2_39_74") (pintype "power_in"))
    )
    (net (code "176") (name "unconnected-(X2-DIO3_8-Pad22)") (class "Default")
      (node (ref "X2") (pin "22") (pinfunction "DIO3_8_22") (pintype "power_in"))
    )
    (net (code "177") (name "unconnected-(X2-DIO3_9-Pad21)") (class "Default")
      (node (ref "X2") (pin "21") (pinfunction "DIO3_9_21") (pintype "power_in"))
    )
    (net (code "178") (name "unconnected-(X2-DIO3_10-Pad20)") (class "Default")
      (node (ref "X2") (pin "20") (pinfunction "DIO3_10_20") (pintype "power_in"))
    )
    (net (code "179") (name "unconnected-(X2-DIO3_11-Pad19)") (class "Default")
      (node (ref "X2") (pin "19") (pinfunction "DIO3_11_19") (pintype "power_in"))
    )
    (net (code "180") (name "unconnected-(X2-DIO3_12-Pad18)") (class "Default")
      (node (ref "X2") (pin "18") (pinfunction "DIO3_12_18") (pintype "power_in"))
    )
    (net (code "181") (name "unconnected-(X2-DIO3_13-Pad17)") (class "Default")
      (node (ref "X2") (pin "17") (pinfunction "DIO3_13_17") (pintype "power_in"))
    )
    (net (code "182") (name "unconnected-(X2-DIO3_14-Pad16)") (class "Default")
      (node (ref "X2") (pin "16") (pinfunction "DIO3_14_16") (pintype "power_in"))
    )
    (net (code "183") (name "unconnected-(X2-DIO3_15-Pad15)") (class "Default")
      (node (ref "X2") (pin "15") (pinfunction "DIO3_15_15") (pintype "power_in"))
    )
    (net (code "184") (name "unconnected-(X2-DIO5_0-Pad14)") (class "Default")
      (node (ref "X2") (pin "14") (pinfunction "DIO5_0_14") (pintype "power_in"))
    )
    (net (code "185") (name "unconnected-(X2-DIO5_1-Pad13)") (class "Default")
      (node (ref "X2") (pin "13") (pinfunction "DIO5_1_13") (pintype "power_in"))
    )
    (net (code "186") (name "unconnected-(X2-DIO5_2-Pad12)") (class "Default")
      (node (ref "X2") (pin "12") (pinfunction "DIO5_2_12") (pintype "power_in"))
    )
    (net (code "187") (name "unconnected-(X2-DIO5_3-Pad11)") (class "Default")
      (node (ref "X2") (pin "11") (pinfunction "DIO5_3_11") (pintype "power_in"))
    )
    (net (code "188") (name "unconnected-(X2-DIO5_4-Pad10)") (class "Default")
      (node (ref "X2") (pin "10") (pinfunction "DIO5_4_10") (pintype "power_in"))
    )
    (net (code "189") (name "unconnected-(X2-DIO5_5-Pad9)") (class "Default")
      (node (ref "X2") (pin "9") (pinfunction "DIO5_5_9") (pintype "power_in"))
    )
    (net (code "190") (name "unconnected-(X2-DIO5_6-Pad8)") (class "Default")
      (node (ref "X2") (pin "8") (pinfunction "DIO5_6_8") (pintype "power_in"))
    )
    (net (code "191") (name "unconnected-(X2-DIO5_7-Pad7)") (class "Default")
      (node (ref "X2") (pin "7") (pinfunction "DIO5_7_7") (pintype "power_in"))
    )
    (net (code "192") (name "unconnected-(X2-DIO5_8-Pad6)") (class "Default")
      (node (ref "X2") (pin "6") (pinfunction "DIO5_8_6") (pintype "power_in"))
    )
    (net (code "193") (name "unconnected-(X2-DIO5_9-Pad5)") (class "Default")
      (node (ref "X2") (pin "5") (pinfunction "DIO5_9_5") (pintype "power_in"))
    )
    (net (code "194") (name "unconnected-(X2-DIO5_10-Pad4)") (class "Default")
      (node (ref "X2") (pin "4") (pinfunction "DIO5_10_4") (pintype "power_in"))
    )
    (net (code "195") (name "unconnected-(X2-DIO5_11-Pad3)") (class "Default")
      (node (ref "X2") (pin "3") (pinfunction "DIO5_11_3") (pintype "power_in"))
    )
    (net (code "196") (name "unconnected-(X2-DIO5_12-Pad2)") (class "Default")
      (node (ref "X2") (pin "2") (pinfunction "DIO5_12_2") (pintype "power_in"))
    )
    (net (code "197") (name "unconnected-(X2-DIO5_13-Pad1)") (class "Default")
      (node (ref "X2") (pin "1") (pinfunction "DIO5_13_1") (pintype "power_in"))
    )
    (net (code "198") (name "unconnected-(X2-DIO5_14-Pad0)") (class "Default")
      (node (ref "X2") (pin "0") (pinfunction "DIO5_14_0") (pintype "power_in"))
    )
    (net (code "199") (name "unconnected-(X2-DIO5_15-Pad99)") (class "Default")
      (node (ref "X2") (pin "99") (pinfunction "DIO5_15_99") (pintype "power_in"))
    )
    (net (code "200") (name "unconnected-(X2-DIO5_16-Pad98)") (class "Default")
      (node (ref "X2") (pin "98") (pinfunction "DIO5_16_98") (pintype "power_in"))
    )
    (net (code "201") (name "unconnected-(X2-DIO5_17-Pad97)") (class "Default")
      (node (ref "X2") (pin "97") (pinfunction "DIO5_17_97") (pintype "power_in"))
    )
    (net (code "202") (name "unconnected-(X2-DIO5_18-Pad96)") (class "Default")
      (node (ref "X2") (pin "96") (pinfunction "DIO5_18_96") (pintype "power_in"))
    )
    (net (code "203") (name "unconnected-(X2-DIO5_19-Pad95)") (class "Default")
      (node (ref "X2") (pin "95") (pinfunction "DIO5_19_95") (pintype "power_in"))
    )
    (net (code "204") (name "unconnected-(X2-DIO5_20-Pad94)") (class "Default")
      (node (ref "X2") (pin "94") (pinfunction "DIO5_20_94") (pintype "power_in"))
    )
    (net (code "205") (name "unconnected-(X2-DIO5_21-Pad93)") (class "Default")
      (node (ref "X2") (pin "93") (pinfunction "DIO5_21_93") (pintype "power_in"))
    )
    (net (code "206") (name "unconnected-(X2-DIO5_22-Pad92)") (class "Default")
      (node (ref "X2") (pin "92") (pinfunction "DIO5_22_92") (pintype "power_in"))
    )
    (net (code "207") (name "unconnected-(X2-DIO5_23-Pad91)") (class "Default")
      (node (ref "X2") (pin "91") (pinfunction "DIO5_23_91") (pintype "power_in"))
    )
    (net (code "208") (name "unconnected-(X2-DIO5_24-Pad90)") (class "Default")
      (node (ref "X2") (pin "90") (pinfunction "DIO5_24_90") (pintype "power_in"))
    )
    (net (code "209") (name "unconnected-(X2-DIO5_25-Pad89)") (class "Default")
      (node (ref "X2") (pin "89") (pinfunction "DIO5_25_89") (pintype "power_in"))
    )
    (net (code "210") (name "unconnected-(X2-DIO5_26-Pad88)") (class "Default")
      (node (ref "X2") (pin "88") (pinfunction "DIO5_26_88") (pintype "power_in"))
    )
    (net (code "211") (name "unconnected-(X2-DIO5_27-Pad87)") (class "Default")
      (node (ref "X2") (pin "87") (pinfunction "DIO5_27_87") (pintype "power_in"))
    )
    (net (code "212") (name "unconnected-(X2-DIO5_28-Pad86)") (class "Default")
      (node (ref "X2") (pin "86") (pinfunction "DIO5_28_86") (pintype "power_in"))
    )
    (net (code "213") (name "unconnected-(X2-DIO5_29-Pad85)") (class "Default")
      (node (ref "X2") (pin "85") (pinfunction "DIO5_29_85") (pintype "power_in"))
    )
    (net (code "214") (name "unconnected-(X2-DIO5_30-Pad84)") (class "Default")
      (node (ref "X2") (pin "84") (pinfunction "DIO5_30_84") (pintype "power_in"))
    )
    (net (code "215") (name "unconnected-(X2-DIO5_31-Pad83)") (class "Default")
      (node (ref "X2") (pin "83") (pinfunction "DIO5_31_83") (pintype "power_in"))
    )
    (net (code "216") (name "unconnected-(X2-DIO5_32-Pad82)") (class "Default")
      (node (ref "X2") (pin "82") (pinfunction "DIO5_32_82") (pintype "power_in"))
    )
    (net (code "217") (name "unconnected-(X2-DIO5_33-Pad81)") (class "Default")
      (node (ref "X2") (pin "81") (pinfunction "DIO5_33_81") (pintype "power_in"))
    )
    (net (code "218") (name "unconnected-(X2-DIO5_34-Pad80)") (class "Default")
      (node (ref "X2") (pin "80") (pinfunction "DIO5_34_80") (pintype "power_in"))
    )
    (net (code "219") (name "unconnected-(X2-DIO5_35-Pad79)") (class "Default")
      (node (ref "X2") (pin "79") (pinfunction "DIO5_35_79") (pintype "power_in"))
    )
    (net (code "220") (name "unconnected-(X2-DIO5_36-Pad78)") (class "Default")
      (node (ref "X2") (pin "78") (pinfunction "DIO5_36_78") (pintype "power_in"))
    )
    (net (code "221") (name "unconnected-(X2-DIO5_37-Pad77)") (class "Default")
      (node (ref "X2") (pin "77") (pinfunction "DIO5_37_77") (pintype "power_in"))
    )
    (net (code "222") (name "unconnected-(X2-DIO5_38-Pad76)") (class "Default")
      (node (ref "X2") (pin "76") (pinfunction "DIO5_38_76") (pintype "power_in"))
    )
    (net (code "223") (name "unconnected-(X2-DIO5_39-Pad75)") (class "Default")
      (node (ref "X2") (pin "75") (pinfunction "DIO5_39_75") (pintype "power_in"))
    )
    (net (code "224") (name "unconnected-(X2-NC-Pad23)") (class "Default")
      (node (ref "X2") (pin "23") (pinfunction "NC_23") (pintype "power_in"))
    )
    (net (code "225") (name "unconnected-(X2-NC-Pad24)") (class "Default")
      (node (ref "X2") (pin "24") (pinfunction "NC_24") (pintype "power_in"))
    )
    (net (code "226") (name "unconnected-(X2-NC-Pad25)") (class "Default")
      (node (ref "X2") (pin "25") (pinfunction "NC_25") (pintype "power_in"))
    )
    (net (code "227") (name "unconnected-(X2-NC-Pad26)") (class "Default")
      (node (ref "X2") (pin "26") (pinfunction "NC_26") (pintype "power_in"))
    )
    (net (code "228") (name "unconnected-(X3-AO0-Pad33)") (class "Default")
      (node (ref "X3") (pin "33") (pinfunction "AO0_33") (pintype "power_in"))
    )
    (net (code "229") (name "unconnected-(X3-AO1-Pad32)") (class "Default")
      (node (ref "X3") (pin "32") (pinfunction "AO1_32") (pintype "power_in"))
    )
    (net (code "230") (name "unconnected-(X3-AO2-Pad31)") (class "Default")
      (node (ref "X3") (pin "31") (pinfunction "AO2_31") (pintype "power_in"))
    )
    (net (code "231") (name "unconnected-(X3-AO3-Pad30)") (class "Default")
      (node (ref "X3") (pin "30") (pinfunction "AO3_30") (pintype "power_in"))
    )
    (net (code "232") (name "unconnected-(X3-AO4-Pad29)") (class "Default")
      (node (ref "X3") (pin "29") (pinfunction "AO4_29") (pintype "power_in"))
    )
    (net (code "233") (name "unconnected-(X3-AO5-Pad28)") (class "Default")
      (node (ref "X3") (pin "28") (pinfunction "AO5_28") (pintype "power_in"))
    )
    (net (code "234") (name "unconnected-(X3-AO6-Pad27)") (class "Default")
      (node (ref "X3") (pin "27") (pinfunction "AO6_27") (pintype "power_in"))
    )
    (net (code "235") (name "unconnected-(X3-AO7-Pad26)") (class "Default")
      (node (ref "X3") (pin "26") (pinfunction "AO7_26") (pintype "power_in"))
    )
    (net (code "236") (name "unconnected-(X3-VCC2-Pad2)") (class "Default")
      (node (ref "X3") (pin "2") (pinfunction "VCC2_2") (pintype "power_in"))
    )
    (net (code "237") (name "unconnected-(X3-VCC2-Pad37)") (class "Default")
      (node (ref "X3") (pin "37") (pinfunction "VCC2_37") (pintype "power_in"))
    )
    (net (code "238") (name "unconnected-(X3-VCC3-Pad3)") (class "Default")
      (node (ref "X3") (pin "3") (pinfunction "VCC3_3") (pintype "power_in"))
    )
    (net (code "239") (name "unconnected-(X3-VCC6-Pad36)") (class "Default")
      (node (ref "X3") (pin "36") (pinfunction "VCC6_36") (pintype "power_in"))
    )
    (net (code "240") (name "unconnected-(X3-VCC8-Pad17)") (class "Default")
      (node (ref "X3") (pin "17") (pinfunction "VCC8_17") (pintype "power_in"))
    )
    (net (code "241") (name "unconnected-(X3-VCC8-Pad22)") (class "Default")
      (node (ref "X3") (pin "22") (pinfunction "VCC8_22") (pintype "power_in"))
    )
    (net (code "242") (name "unconnected-(X3-VCC9-Pad16)") (class "Default")
      (node (ref "X3") (pin "16") (pinfunction "VCC9_16") (pintype "power_in"))
    )
    (net (code "243") (name "unconnected-(X3-VCC11-Pad14)") (class "Default")
      (node (ref "X3") (pin "14") (pinfunction "VCC11_14") (pintype "power_in"))
    )
    (net (code "244") (name "unconnected-(X3-VCC11-Pad25)") (class "Default")
      (node (ref "X3") (pin "25") (pinfunction "VCC11_25") (pintype "power_in"))
    )
    (net (code "245") (name "unconnected-(X3-VCC12-Pad23)") (class "Default")
      (node (ref "X3") (pin "23") (pinfunction "VCC12_23") (pintype "power_in"))
    )
  )
)
